# Converter_PWM_to_Voltage.net
KiCad netlist of a schematic drawn in Altium Designer
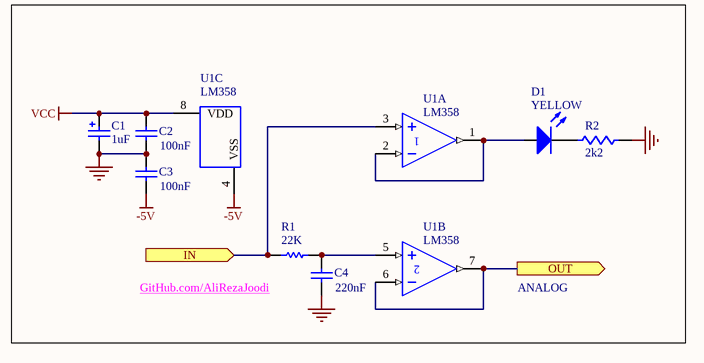
[diagram p0: Converter_PWM to Voltage.SchDoc]

(export (version "E")
  (design (tool "Eeschema 10.0.6"))
  (components
    (comp (ref "C1")
      (value "1uF")
      (footprint "Cap_A")
      (description "Polarized Capacitor (Radial)")
      (fields
        (field (name "MANUFACTURER") "Generic Components")
        (field (name "Comment") "Cap Pol1")
        (field (name "PUBLISHER") "Altium Limited")
      )
      (libsource (lib "Miscellaneous Devices") (part "Cap Pol1"))
    )
    (comp (ref "C2")
      (value "100nF")
      (footprint "0805")
      (description "Capacitor")
      (fields (field (name "Comment") "Cap") (field (name "PUBLISHER") "Altium Limited"))
      (libsource (lib "Miscellaneous Devices") (part "Cap"))
    )
    (comp (ref "C3")
      (value "100nF")
      (footprint "0805")
      (description "Capacitor")
      (fields (field (name "Comment") "Cap") (field (name "PUBLISHER") "Altium Limited"))
      (libsource (lib "Miscellaneous Devices") (part "Cap"))
    )
    (comp (ref "C4")
      (value "220nF")
      (footprint "0805")
      (description "Capacitor")
      (fields (field (name "Comment") "Cap") (field (name "PUBLISHER") "Altium Limited"))
      (libsource (lib "Miscellaneous Devices") (part "Cap"))
    )
    (comp (ref "D1")
      (value "YELLOW")
      (footprint "0805_Diode")
      (description "Typical INFRARED GaAs LED")
      (fields (field (name "MANUFACTURER") "Generic Components") (field (name "PUBLISHER") "Altium Limited"))
      (libsource (lib "Miscellaneous Devices") (part "LED"))
    )
    (comp (ref "R1")
      (value "22K")
      (footprint "0805")
      (description "Resistor")
      (fields (field (name "Comment") "Res1") (field (name "PUBLISHER") "Altium Limited"))
      (libsource (lib "Miscellaneous Devices") (part "Res1"))
    )
    (comp (ref "R2")
      (value "2k2")
      (footprint "0805")
      (description "Resistor")
      (fields
        (field (name "MANUFACTURER") "Generic Components")
        (field (name "Comment") "RES")
        (field (name "PUBLISHER") "Altium Limited")
      )
      (libsource (lib "") (part "Res1_1"))
    )
    (comp (ref "U1")
      (value "LM358")
      (footprint "SOP127P636-8N")
      (description "Dual Low-Power Operational Amplifier")
      (fields (field (name "PUBLISHER") "Altium Limited"))
      (libsource (lib "my Libraries") (part "LM358"))
    )
  )
  (nets
    (net (code "1") (name "-5V") (class "Default")
      (node (ref "C3") (pin "2") (pinfunction "2_2") (pintype "passive"))
      (node (ref "U1") (pin "4") (pinfunction "VSS_4") (pintype "power_in"))
    )
    (net (code "2") (name "/IN") (class "Default")
      (node (ref "R1") (pin "1") (pinfunction "1_1") (pintype "passive"))
      (node (ref "U1") (pin "3") (pinfunction "IN+_3") (pintype "input"))
    )
    (net (code "3") (name "/OUT") (class "Default")
      (node (ref "U1") (pin "6") (pinfunction "IN-_6") (pintype "input"))
      (node (ref "U1") (pin "7") (pinfunction "OUT_7") (pintype "output"))
    )
    (net (code "4") (name "GND") (class "Default")
      (node (ref "C1") (pin "2") (pinfunction "2_2") (pintype "passive"))
      (node (ref "C2") (pin "2") (pinfunction "2_2") (pintype "passive"))
      (node (ref "C3") (pin "1") (pinfunction "1_1") (pintype "passive"))
      (node (ref "C4") (pin "1") (pinfunction "1_1") (pintype "passive"))
      (node (ref "R2") (pin "2") (pinfunction "2_2") (pintype "passive"))
    )
    (net (code "5") (name "Net-(D1-A)") (class "Default")
      (node (ref "D1") (pin "1") (pinfunction "A_1") (pintype "passive"))
      (node (ref "U1") (pin "1") (pinfunction "OUT_1") (pintype "output"))
      (node (ref "U1") (pin "2") (pinfunction "IN-_2") (pintype "input"))
    )
    (net (code "6") (name "Net-(D1-K)") (class "Default")
      (node (ref "D1") (pin "2") (pinfunction "K_2") (pintype "passive"))
      (node (ref "R2") (pin "1") (pinfunction "1_1") (pintype "passive"))
    )
    (net (code "7") (name "Net-(U1B-IN+)") (class "Default")
      (node (ref "C4") (pin "2") (pinfunction "2_2") (pintype "passive"))
      (node (ref "R1") (pin "2") (pinfunction "2_2") (pintype "passive"))
      (node (ref "U1") (pin "5") (pinfunction "IN+_5") (pintype "input"))
    )
    (net (code "8") (name "VCC") (class "Default")
      (node (ref "C1") (pin "1") (pinfunction "1_1") (pintype "passive"))
      (node (ref "C2") (pin "1") (pinfunction "1_1") (pintype "passive"))
      (node (ref "U1") (pin "8") (pinfunction "VDD_8") (pintype "passive"))
    )
  )
)
